# PWR_IN.net
KiCad netlist of a schematic drawn in Altium Designer
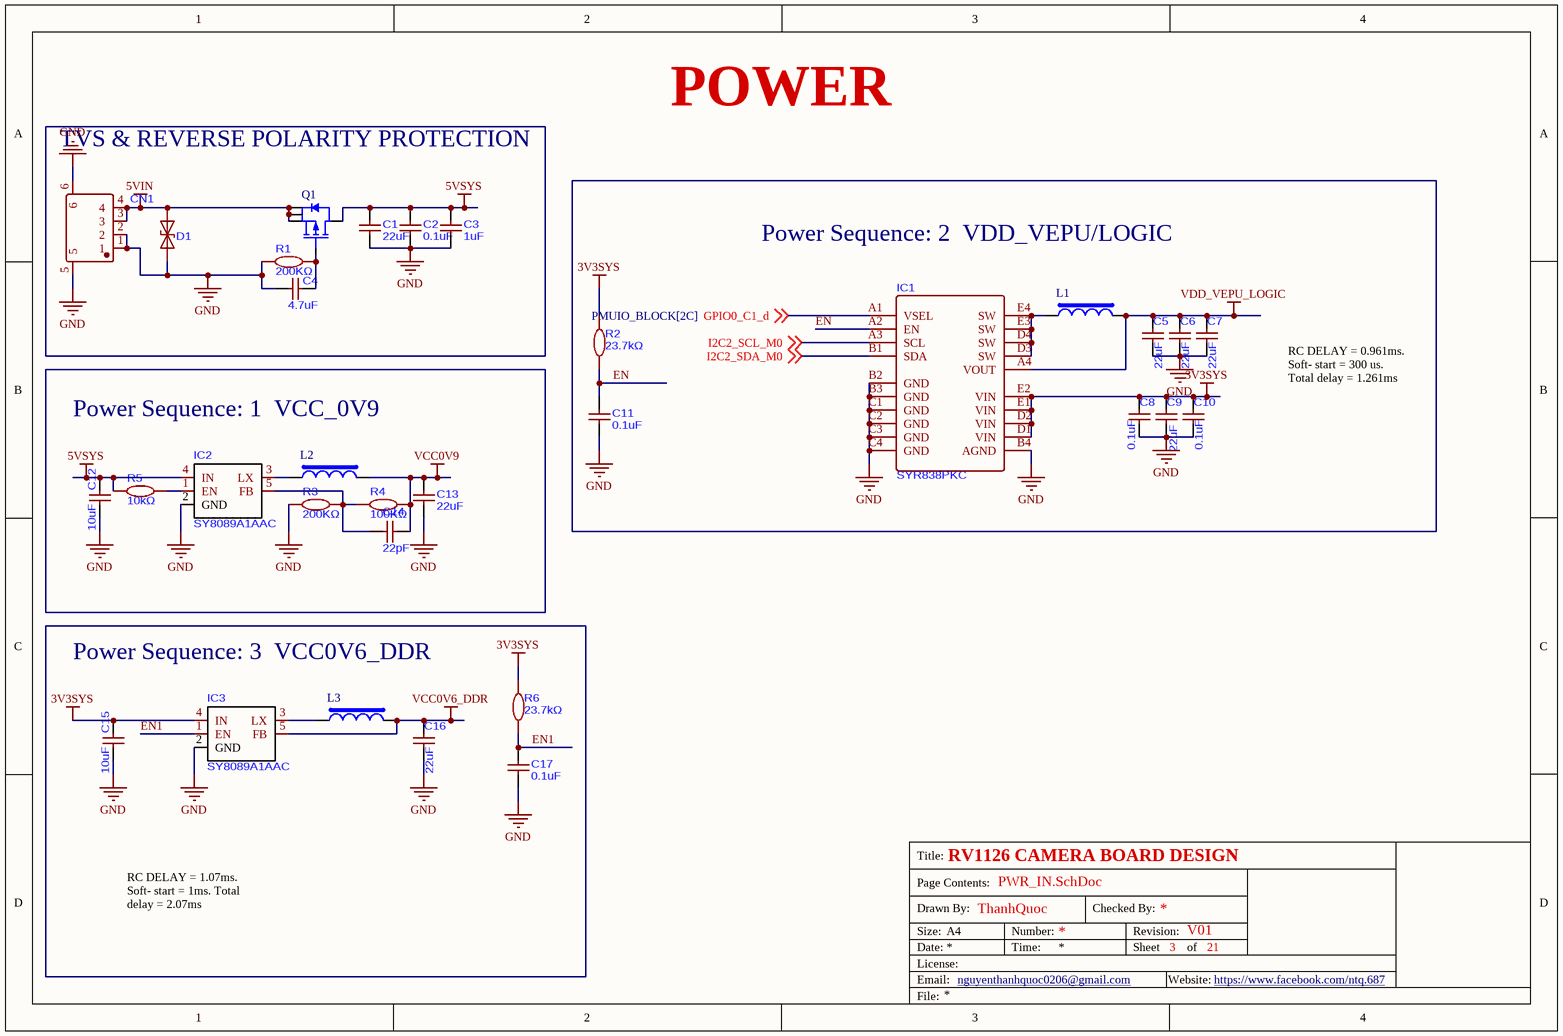
[diagram p0: PWR_IN.SchDoc]

(export (version "E")
  (design (tool "Eeschema 10.0.6"))
  (components
    (comp (ref "C1")
      (value "22uF")
      (footprint "C0603")
      (description "22uF ±20% 25V Ceramic Capacitor X5R 0603")
      (libsource (lib "Schlib1") (part "CAP_22uF-25V-20%-0603"))
    )
    (comp (ref "C2")
      (value "0.1uF")
      (footprint "C0201")
      (description "CAP CER 100nF 16V X5R 0201")
      (libsource (lib "Schlib1") (part "CAP_100nF-16V-10%-0201"))
    )
    (comp (ref "C3")
      (value "1uF")
      (footprint "C0201")
      (description "1uF ±10% 10V Ceramic Capacitor X5R 0201")
      (libsource (lib "Schlib1") (part "CAP_1uF-10V-10%-0201"))
    )
    (comp (ref "C4")
      (value "4.7uF")
      (footprint "C0402")
      (description "4.7uF ±10% 16V Ceramic Capacitor X5R 0402")
      (libsource (lib "Schlib1") (part "CAP_4.7uF-16V-10%-0402"))
    )
    (comp (ref "C5")
      (value "22uF")
      (footprint "C0402")
      (description "22uF X5R ±20% 10V 0402 Ceramic Capacitors RoHS")
      (libsource (lib "Schlib1") (part "CAP_22uF-10V-20%-0402"))
    )
    (comp (ref "C6")
      (value "22uF")
      (footprint "C0402")
      (description "22uF X5R ±20% 10V 0402 Ceramic Capacitors RoHS")
      (libsource (lib "Schlib1") (part "CAP_22uF-10V-20%-0402"))
    )
    (comp (ref "C7")
      (value "22uF")
      (footprint "C0402")
      (description "22uF X5R ±20% 10V 0402 Ceramic Capacitors RoHS")
      (libsource (lib "Schlib1") (part "CAP_22uF-10V-20%-0402"))
    )
    (comp (ref "C8")
      (value "0.1uF")
      (footprint "C0201")
      (description "CAP CER 100nF 16V X5R 0201")
      (libsource (lib "Schlib1") (part "CAP_100nF-16V-10%-0201"))
    )
    (comp (ref "C9")
      (value "22uF")
      (footprint "C0603")
      (description "22uF ±20% 16V Ceramic Capacitor X5R 0603")
      (libsource (lib "Schlib1") (part "CAP_22uF-16V-20%-0603"))
    )
    (comp (ref "C10")
      (value "0.1uF")
      (footprint "C0201")
      (description "CAP CER 100nF 16V X5R 0201")
      (libsource (lib "Schlib1") (part "CAP_100nF-16V-10%-0201"))
    )
    (comp (ref "C11")
      (value "0.1uF")
      (footprint "C0201")
      (description "CAP CER 100nF 16V X5R 0201")
      (libsource (lib "Schlib1") (part "CAP_100nF-16V-10%-0201"))
    )
    (comp (ref "C12")
      (value "10uF")
      (footprint "C0402")
      (description "10µF ±20% 10V Ceramic Capacitor X5R 0402 (1005 Metric)")
      (libsource (lib "Schlib1") (part "CAP_10uF-10V-20%-0402"))
    )
    (comp (ref "C13")
      (value "22uF")
      (footprint "C0402")
      (description "22uF X5R ±20% 10V 0402 Ceramic Capacitors RoHS")
      (libsource (lib "Schlib1") (part "CAP_22uF-10V-20%-0402"))
    )
    (comp (ref "C14")
      (value "22pF")
      (footprint "C0201")
      (description "CAP CER 22pF 50V NP0 0201")
      (libsource (lib "Schlib1") (part "CAP_22pF-50V-5%-0201"))
    )
    (comp (ref "C15")
      (value "10uF")
      (footprint "C0402")
      (description "10µF ±20% 10V Ceramic Capacitor X5R 0402 (1005 Metric)")
      (libsource (lib "Schlib1") (part "CAP_10uF-10V-20%-0402"))
    )
    (comp (ref "C16")
      (value "22uF")
      (footprint "C0402")
      (description "22uF X5R ±20% 10V 0402 Ceramic Capacitors RoHS")
      (libsource (lib "Schlib1") (part "CAP_22uF-10V-20%-0402"))
    )
    (comp (ref "C17")
      (value "0.1uF")
      (footprint "C0201")
      (description "CAP CER 100nF 16V X5R 0201")
      (libsource (lib "Schlib1") (part "CAP_100nF-16V-10%-0201"))
    )
    (comp (ref "CN1")
      (value "SMD,P=2mm,Surface Mount,Right Angle")
      (footprint "CONN-SMD_4P-P2.00_WTBA0-BH004")
      (libsource (lib "Schlib1") (part "5023520401"))
    )
    (comp (ref "D1")
      (value "TVS DIODE 5VWM 10VC X1-SON-2(0.6x1)")
      (footprint "X1SON-2_L1.0-W0.6-P0.65-BI-1")
      (libsource (lib "Schlib1") (part "LTVS8H5.0CAT5G"))
    )
    (comp (ref "IC1")
      (value "SYR838PKC")
      (footprint "BGA-20_L15.6-W2.0-R4-C6-P0.40-BL")
      (description "High-efficiency 5.5V, 6A, 2.4MHz synchronous buck regulator")
      (libsource (lib "Schlib1") (part "SYR838PKC"))
    )
    (comp (ref "IC2")
      (value "SY8089A1AAC")
      (footprint "SOT-23-5_L3.0-W1.7-P0.95-LS2.8-BR")
      (description "High Efficiency, 1.5MHz, 2A Synchronous Step Down Regulator")
      (libsource (lib "Schlib1") (part "SY8089A1AAC"))
    )
    (comp (ref "IC3")
      (value "SY8089A1AAC")
      (footprint "SOT-23-5_L3.0-W1.7-P0.95-LS2.8-BR")
      (description "High Efficiency, 1.5MHz, 2A Synchronous Step Down Regulator")
      (libsource (lib "Schlib1") (part "SY8089A1AAC"))
    )
    (comp (ref "L1")
      (value "FTC252012SR47MBCA")
      (footprint "IND_1008")
      (description "FIXED IND 0.47uH 6.5A 13mΩ SMD,2x2.5mm")
      (fields
        (field (name "MANUFACTURER") "Murata Electronics")
        (field (name "MANUFACTURER PART NUMBER") "DFE252010P-R47M=P2")
      )
      (libsource (lib "Schlib1") (part "IND_470nH-6.5A-20%-1008"))
    )
    (comp (ref "L2")
      (value "APH252012C1R0MP01")
      (footprint "IND_1008")
      (description "FIXED IND 01uH 4A 35mΩ SMD,2x2.5mm")
      (fields
        (field (name "MANUFACTURER") "Murata Electronics")
        (field (name "MANUFACTURER PART NUMBER") "DFE252010P-R47M=P2")
      )
      (libsource (lib "Schlib1") (part "IND_1uH-4A-20%-1008"))
    )
    (comp (ref "L3")
      (value "APH252012C1R0MP01")
      (footprint "IND_1008")
      (description "FIXED IND 01uH 4A 35mΩ SMD,2x2.5mm")
      (fields
        (field (name "MANUFACTURER") "Murata Electronics")
        (field (name "MANUFACTURER PART NUMBER") "DFE252010P-R47M=P2")
      )
      (libsource (lib "Schlib1") (part "IND_1uH-4A-20%-1008"))
    )
    (comp (ref "Q1")
      (value "SI7615CDN-T1-GE3")
      (footprint "PowerPAK_1212-8_SMD")
      (description "22W 20V 60A 700mV 7mΩ@4.5V 1 P-Channel P-Channel DFN-8L(3x3) Single FETs, MOSFETs RoHS")
      (fields (field (name "MANUFACTURER") "Vishay Siliconix"))
      (libsource (lib "Schlib1") (part "SI7615CDN-T1-GE3-MS"))
    )
    (comp (ref "R1")
      (value "200KΩ")
      (footprint "R0201")
      (description "RES 200kΩ ±1% 50mW 0201")
      (libsource (lib "Schlib1") (part "RES_200K-50mW-1%-0201"))
    )
    (comp (ref "R2")
      (value "23.7kΩ")
      (footprint "R0402")
      (description "RES 23700Ω ±0.1% 0.063W 0402")
      (libsource (lib "Schlib1") (part "RES_23.7K-0.063W-0.1%-0402"))
    )
    (comp (ref "R3")
      (value "200KΩ")
      (footprint "R0201")
      (description "RES 200kΩ ±1% 50mW 0201")
      (libsource (lib "Schlib1") (part "RES_200K-50mW-1%-0201"))
    )
    (comp (ref "R4")
      (value "100KΩ")
      (footprint "R0201")
      (description "RES 100kΩ ±1% 50mW 0201")
      (libsource (lib "Schlib1") (part "RES_100K-50mW-1%-0201"))
    )
    (comp (ref "R5")
      (value "10kΩ")
      (footprint "R0201")
      (description "RES 10KΩ ±1% 50mW 0201")
      (libsource (lib "Schlib1") (part "RES_10K-50mW-1%-0201"))
    )
    (comp (ref "R6")
      (value "23.7kΩ")
      (footprint "R0402")
      (description "RES 23700Ω ±0.1% 0.063W 0402")
      (libsource (lib "Schlib1") (part "RES_23.7K-0.063W-0.1%-0402"))
    )
  )
  (nets
    (net (code "1") (name "/EN") (class "Default")
      (node (ref "C11") (pin "2") (pinfunction "2_2") (pintype "passive"))
      (node (ref "IC1") (pin "A2") (pinfunction "EN_A2") (pintype "passive"))
      (node (ref "R2") (pin "1") (pinfunction "1_1") (pintype "passive"))
    )
    (net (code "2") (name "/EN1") (class "Default")
      (node (ref "C17") (pin "2") (pinfunction "2_2") (pintype "passive"))
      (node (ref "IC3") (pin "1") (pinfunction "EN_1") (pintype "passive"))
      (node (ref "R6") (pin "1") (pinfunction "1_1") (pintype "passive"))
    )
    (net (code "3") (name "3V3SYS") (class "Default")
      (node (ref "C10") (pin "2") (pinfunction "2_2") (pintype "passive"))
      (node (ref "C15") (pin "2") (pinfunction "2_2") (pintype "passive"))
      (node (ref "C8") (pin "2") (pinfunction "2_2") (pintype "passive"))
      (node (ref "C9") (pin "2") (pinfunction "2_2") (pintype "passive"))
      (node (ref "IC1") (pin "D1") (pinfunction "VIN_D1") (pintype "passive"))
      (node (ref "IC1") (pin "D2") (pinfunction "VIN_D2") (pintype "passive"))
      (node (ref "IC1") (pin "E1") (pinfunction "VIN_E1") (pintype "passive"))
      (node (ref "IC1") (pin "E2") (pinfunction "VIN_E2") (pintype "passive"))
      (node (ref "IC3") (pin "4") (pinfunction "IN_4") (pintype "passive"))
      (node (ref "R2") (pin "2") (pinfunction "2_2") (pintype "passive"))
      (node (ref "R6") (pin "2") (pinfunction "2_2") (pintype "passive"))
    )
    (net (code "4") (name "5VIN") (class "Default")
      (node (ref "CN1") (pin "3") (pinfunction "3_3") (pintype "passive"))
      (node (ref "CN1") (pin "4") (pinfunction "4_4") (pintype "passive"))
      (node (ref "D1") (pin "2") (pinfunction "A_2") (pintype "passive"))
      (node (ref "Q1") (pin "1") (pinfunction "S_1") (pintype "passive"))
      (node (ref "Q1") (pin "2") (pinfunction "S_2") (pintype "passive"))
      (node (ref "Q1") (pin "3") (pinfunction "S_3") (pintype "passive"))
    )
    (net (code "5") (name "5VSYS") (class "Default")
      (node (ref "C1") (pin "2") (pinfunction "2_2") (pintype "passive"))
      (node (ref "C12") (pin "2") (pinfunction "2_2") (pintype "passive"))
      (node (ref "C2") (pin "2") (pinfunction "2_2") (pintype "passive"))
      (node (ref "C3") (pin "2") (pinfunction "2_2") (pintype "passive"))
      (node (ref "IC2") (pin "4") (pinfunction "IN_4") (pintype "passive"))
      (node (ref "Q1") (pin "5") (pinfunction "D_5") (pintype "passive"))
      (node (ref "R5") (pin "1") (pinfunction "1_1") (pintype "passive"))
    )
    (net (code "6") (name "GND") (class "Default")
      (node (ref "C1") (pin "1") (pinfunction "1_1") (pintype "passive"))
      (node (ref "C10") (pin "1") (pinfunction "1_1") (pintype "passive"))
      (node (ref "C11") (pin "1") (pinfunction "1_1") (pintype "passive"))
      (node (ref "C12") (pin "1") (pinfunction "1_1") (pintype "passive"))
      (node (ref "C13") (pin "1") (pinfunction "1_1") (pintype "passive"))
      (node (ref "C15") (pin "1") (pinfunction "1_1") (pintype "passive"))
      (node (ref "C16") (pin "1") (pinfunction "1_1") (pintype "passive"))
      (node (ref "C17") (pin "1") (pinfunction "1_1") (pintype "passive"))
      (node (ref "C2") (pin "1") (pinfunction "1_1") (pintype "passive"))
      (node (ref "C3") (pin "1") (pinfunction "1_1") (pintype "passive"))
      (node (ref "C4") (pin "2") (pinfunction "2_2") (pintype "passive"))
      (node (ref "C5") (pin "1") (pinfunction "1_1") (pintype "passive"))
      (node (ref "C6") (pin "1") (pinfunction "1_1") (pintype "passive"))
      (node (ref "C7") (pin "1") (pinfunction "1_1") (pintype "passive"))
      (node (ref "C8") (pin "1") (pinfunction "1_1") (pintype "passive"))
      (node (ref "C9") (pin "1") (pinfunction "1_1") (pintype "passive"))
      (node (ref "CN1") (pin "1") (pinfunction "1_1") (pintype "passive"))
      (node (ref "CN1") (pin "2") (pinfunction "2_2") (pintype "passive"))
      (node (ref "CN1") (pin "5") (pinfunction "5_5") (pintype "passive"))
      (node (ref "CN1") (pin "6") (pinfunction "6_6") (pintype "passive"))
      (node (ref "D1") (pin "1") (pinfunction "K_1") (pintype "passive"))
      (node (ref "IC1") (pin "B2") (pinfunction "GND_B2") (pintype "passive"))
      (node (ref "IC1") (pin "B3") (pinfunction "GND_B3") (pintype "passive"))
      (node (ref "IC1") (pin "B4") (pinfunction "AGND_B4") (pintype "passive"))
      (node (ref "IC1") (pin "C1") (pinfunction "GND_C1") (pintype "passive"))
      (node (ref "IC1") (pin "C2") (pinfunction "GND_C2") (pintype "passive"))
      (node (ref "IC1") (pin "C3") (pinfunction "GND_C3") (pintype "passive"))
      (node (ref "IC1") (pin "C4") (pinfunction "GND_C4") (pintype "passive"))
      (node (ref "IC2") (pin "2") (pinfunction "GND_2") (pintype "passive"))
      (node (ref "IC3") (pin "2") (pinfunction "GND_2") (pintype "passive"))
      (node (ref "R1") (pin "1") (pinfunction "1_1") (pintype "passive"))
      (node (ref "R3") (pin "1") (pinfunction "1_1") (pintype "passive"))
    )
    (net (code "7") (name "GPIO0_C1_d") (class "Default")
      (node (ref "IC1") (pin "A1") (pinfunction "VSEL_A1") (pintype "passive"))
    )
    (net (code "8") (name "I2C2_SCL_M0") (class "Default")
      (node (ref "IC1") (pin "A3") (pinfunction "SCL_A3") (pintype "passive"))
    )
    (net (code "9") (name "I2C2_SDA_M0") (class "Default")
      (node (ref "IC1") (pin "B1") (pinfunction "SDA_B1") (pintype "passive"))
    )
    (net (code "10") (name "Net-(IC1-SW-PadD3)") (class "Default")
      (node (ref "IC1") (pin "D3") (pinfunction "SW_D3") (pintype "passive"))
      (node (ref "IC1") (pin "D4") (pinfunction "SW_D4") (pintype "passive"))
      (node (ref "IC1") (pin "E3") (pinfunction "SW_E3") (pintype "passive"))
      (node (ref "IC1") (pin "E4") (pinfunction "SW_E4") (pintype "passive"))
      (node (ref "L1") (pin "1") (pinfunction "1_1") (pintype "passive"))
    )
    (net (code "11") (name "Net-(IC2-EN)") (class "Default")
      (node (ref "IC2") (pin "1") (pinfunction "EN_1") (pintype "passive"))
      (node (ref "R5") (pin "2") (pinfunction "2_2") (pintype "passive"))
    )
    (net (code "12") (name "Net-(IC2-FB)") (class "Default")
      (node (ref "C14") (pin "1") (pinfunction "1_1") (pintype "passive"))
      (node (ref "IC2") (pin "5") (pinfunction "FB_5") (pintype "passive"))
      (node (ref "R3") (pin "2") (pinfunction "2_2") (pintype "passive"))
      (node (ref "R4") (pin "1") (pinfunction "1_1") (pintype "passive"))
    )
    (net (code "13") (name "Net-(IC2-LX)") (class "Default")
      (node (ref "IC2") (pin "3") (pinfunction "LX_3") (pintype "passive"))
      (node (ref "L2") (pin "1") (pinfunction "1_1") (pintype "passive"))
    )
    (net (code "14") (name "Net-(IC3-LX)") (class "Default")
      (node (ref "IC3") (pin "3") (pinfunction "LX_3") (pintype "passive"))
      (node (ref "L3") (pin "1") (pinfunction "1_1") (pintype "passive"))
    )
    (net (code "15") (name "Net-(Q1-G)") (class "Default")
      (node (ref "C4") (pin "1") (pinfunction "1_1") (pintype "passive"))
      (node (ref "Q1") (pin "4") (pinfunction "G_4") (pintype "passive"))
      (node (ref "R1") (pin "2") (pinfunction "2_2") (pintype "passive"))
    )
    (net (code "16") (name "VCC0V6_DDR") (class "Default")
      (node (ref "C16") (pin "2") (pinfunction "2_2") (pintype "passive"))
      (node (ref "IC3") (pin "5") (pinfunction "FB_5") (pintype "passive"))
      (node (ref "L3") (pin "2") (pinfunction "2_2") (pintype "passive"))
    )
    (net (code "17") (name "VCC0V9") (class "Default")
      (node (ref "C13") (pin "2") (pinfunction "2_2") (pintype "passive"))
      (node (ref "C14") (pin "2") (pinfunction "2_2") (pintype "passive"))
      (node (ref "L2") (pin "2") (pinfunction "2_2") (pintype "passive"))
      (node (ref "R4") (pin "2") (pinfunction "2_2") (pintype "passive"))
    )
    (net (code "18") (name "VDD_VEPU_LOGIC") (class "Default")
      (node (ref "C5") (pin "2") (pinfunction "2_2") (pintype "passive"))
      (node (ref "C6") (pin "2") (pinfunction "2_2") (pintype "passive"))
      (node (ref "C7") (pin "2") (pinfunction "2_2") (pintype "passive"))
      (node (ref "IC1") (pin "A4") (pinfunction "VOUT_A4") (pintype "passive"))
      (node (ref "L1") (pin "2") (pinfunction "2_2") (pintype "passive"))
    )
  )
)
